# ledcurrentdriver.net
KiCad netlist of a schematic drawn in Altium Designer
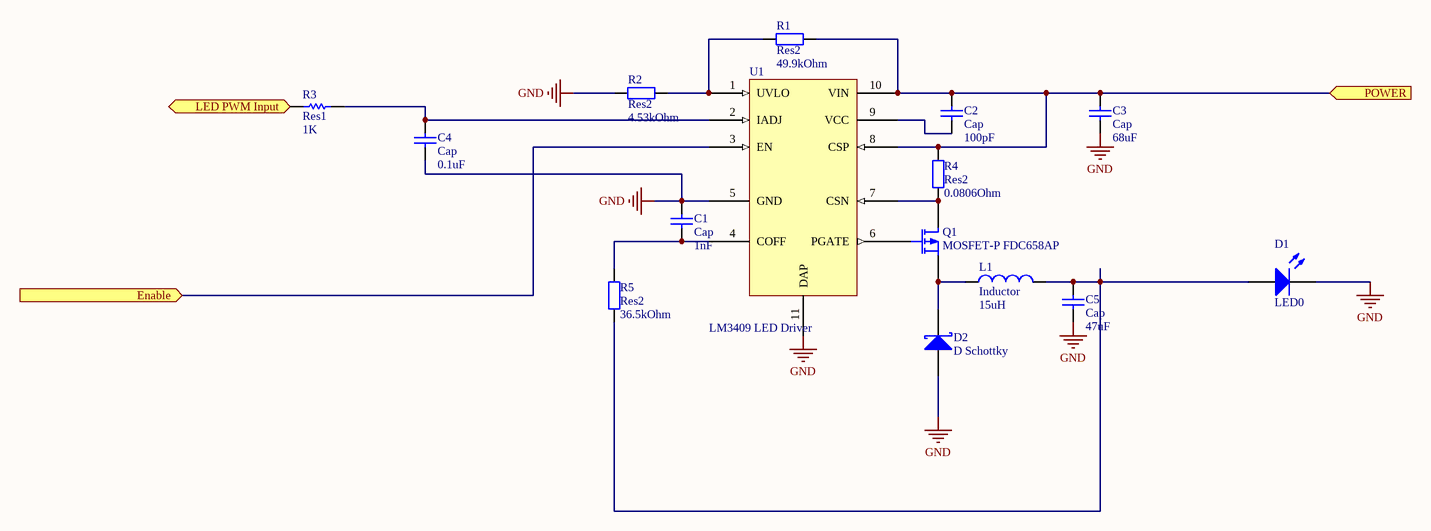
[diagram p0: ledcurrentdriver.SchDoc]

(export (version "E")
  (design (tool "Eeschema 10.0.6"))
  (components
    (comp (ref "C1")
      (value "Cap")
      (footprint "RAD-0.3")
      (description "Capacitor")
      (fields (field (name "ALTIUM_VALUE") "1nF") (field (name "PUBLISHER") "Altium Limited"))
      (libsource (lib "Miscellaneous Devices") (part "Cap"))
    )
    (comp (ref "C2")
      (value "Cap")
      (footprint "RAD-0.3")
      (description "Capacitor")
      (fields (field (name "ALTIUM_VALUE") "100pF") (field (name "PUBLISHER") "Altium Limited"))
      (libsource (lib "Miscellaneous Devices") (part "Cap"))
    )
    (comp (ref "C3")
      (value "Cap")
      (footprint "RAD-0.3")
      (description "Capacitor")
      (fields (field (name "ALTIUM_VALUE") "68uF") (field (name "PUBLISHER") "Altium Limited"))
      (libsource (lib "Miscellaneous Devices") (part "Cap"))
    )
    (comp (ref "C4")
      (value "Cap")
      (footprint "RAD-0.3")
      (description "Capacitor")
      (fields (field (name "ALTIUM_VALUE") "0.1uF") (field (name "PUBLISHER") "Altium Limited"))
      (libsource (lib "Miscellaneous Devices") (part "Cap"))
    )
    (comp (ref "C5")
      (value "Cap")
      (footprint "RAD-0.3")
      (description "Capacitor")
      (fields (field (name "ALTIUM_VALUE") "47uF") (field (name "PUBLISHER") "Altium Limited"))
      (libsource (lib "Miscellaneous Devices") (part "Cap"))
    )
    (comp (ref "D1")
      (value "LED0")
      (footprint "SML-01 (ROHM LED SERIES)")
      (description "Typical INFRARED GaAs LED")
      (fields (field (name "PUBLISHER") "Altium Limited"))
      (libsource (lib "Miscellaneous Devices") (part "LED0"))
    )
    (comp (ref "D2")
      (value "D Schottky")
      (footprint "SMB")
      (description "Schottky Diode")
      (fields (field (name "PUBLISHER") "Altium Limited"))
      (libsource (lib "Miscellaneous Devices") (part "D Schottky"))
    )
    (comp (ref "L1")
      (value "Inductor")
      (footprint "0402-A")
      (fields (field (name "ALTIUM_VALUE") "15uH") (field (name "PUBLISHER") "Altium Limited"))
      (libsource (lib "Miscellaneous Devices") (part "Inductor"))
    )
    (comp (ref "Q1")
      (value "MOSFET-P FDC658AP")
      (footprint "E3")
      (description "P-Channel MOSFET")
      (fields (field (name "PUBLISHER") "Altium Limited"))
      (libsource (lib "Miscellaneous Devices") (part "MOSFET-P"))
    )
    (comp (ref "R1")
      (value "Res2")
      (footprint "AXIAL-0.4")
      (description "Resistor")
      (fields (field (name "ALTIUM_VALUE") "49.9kOhm") (field (name "PUBLISHER") "Altium Limited"))
      (libsource (lib "") (part "Res2_1"))
    )
    (comp (ref "R2")
      (value "Res2")
      (footprint "AXIAL-0.4")
      (description "Resistor")
      (fields (field (name "ALTIUM_VALUE") "4.53kOhm") (field (name "PUBLISHER") "Altium Limited"))
      (libsource (lib "") (part "Res2_1"))
    )
    (comp (ref "R3")
      (value "Res1")
      (footprint "AXIAL-0.3")
      (description "Resistor")
      (fields (field (name "ALTIUM_VALUE") "1K") (field (name "PUBLISHER") "Altium Limited"))
      (libsource (lib "Miscellaneous Devices") (part "Res1"))
    )
    (comp (ref "R4")
      (value "Res2")
      (footprint "AXIAL-0.4")
      (description "Resistor")
      (fields (field (name "ALTIUM_VALUE") "0.0806Ohm") (field (name "PUBLISHER") "Altium Limited"))
      (libsource (lib "Miscellaneous Devices") (part "Res2"))
    )
    (comp (ref "R5")
      (value "Res2")
      (footprint "AXIAL-0.4")
      (description "Resistor")
      (fields (field (name "ALTIUM_VALUE") "36.5kOhm") (field (name "PUBLISHER") "Altium Limited"))
      (libsource (lib "Miscellaneous Devices") (part "Res2"))
    )
    (comp (ref "U1")
      (value "LM3409 LED Driver")
      (footprint "10eMSOP + thermal pad - LM3409")
      (description "PFET Buck Controller for High Power LED Drivers")
      (libsource (lib "LM3409") (part "LM3409"))
    )
  )
  (nets
    (net (code "1") (name "/Enable") (class "Default")
      (node (ref "U1") (pin "3") (pinfunction "EN_3") (pintype "input"))
    )
    (net (code "2") (name "/LED PWM Input") (class "Default")
      (node (ref "R3") (pin "1") (pinfunction "1_1") (pintype "passive"))
    )
    (net (code "5") (name "/POWER") (class "Default")
      (node (ref "C2") (pin "2") (pinfunction "2_2") (pintype "passive"))
      (node (ref "C3") (pin "2") (pinfunction "2_2") (pintype "passive"))
      (node (ref "R1") (pin "2") (pinfunction "2_2") (pintype "passive"))
      (node (ref "R4") (pin "2") (pinfunction "2_2") (pintype "passive"))
      (node (ref "U1") (pin "10") (pinfunction "VIN_10") (pintype "passive"))
      (node (ref "U1") (pin "8") (pinfunction "CSP_8") (pintype "input"))
    )
    (net (code "6") (name "GND") (class "Default")
      (node (ref "C1") (pin "2") (pinfunction "2_2") (pintype "passive"))
      (node (ref "C3") (pin "1") (pinfunction "1_1") (pintype "passive"))
      (node (ref "C4") (pin "2") (pinfunction "2_2") (pintype "passive"))
      (node (ref "C5") (pin "1") (pinfunction "1_1") (pintype "passive"))
      (node (ref "D1") (pin "2") (pinfunction "K_2") (pintype "passive"))
      (node (ref "D2") (pin "1") (pinfunction "A_1") (pintype "passive"))
      (node (ref "R2") (pin "1") (pinfunction "1_1") (pintype "passive"))
      (node (ref "U1") (pin "11") (pinfunction "DAP_11") (pintype "power_in"))
      (node (ref "U1") (pin "5") (pinfunction "GND_5") (pintype "power_in"))
    )
    (net (code "7") (name "Net-(D1-A)") (class "Default")
      (node (ref "C5") (pin "2") (pinfunction "2_2") (pintype "passive"))
      (node (ref "D1") (pin "1") (pinfunction "A_1") (pintype "passive"))
      (node (ref "L1") (pin "2") (pinfunction "2_2") (pintype "passive"))
      (node (ref "R5") (pin "1") (pinfunction "1_1") (pintype "passive"))
    )
    (net (code "8") (name "Net-(D2-K)") (class "Default")
      (node (ref "D2") (pin "2") (pinfunction "K_2") (pintype "passive"))
      (node (ref "L1") (pin "1") (pinfunction "1_1") (pintype "passive"))
      (node (ref "Q1") (pin "3") (pinfunction "S_3") (pintype "passive"))
    )
    (net (code "9") (name "Net-(Q1-D)") (class "Default")
      (node (ref "Q1") (pin "1") (pinfunction "D_1") (pintype "passive"))
      (node (ref "R4") (pin "1") (pinfunction "1_1") (pintype "passive"))
      (node (ref "U1") (pin "7") (pinfunction "CSN_7") (pintype "input"))
    )
    (net (code "10") (name "Net-(U1-COFF)") (class "Default")
      (node (ref "C1") (pin "1") (pinfunction "1_1") (pintype "passive"))
      (node (ref "R5") (pin "2") (pinfunction "2_2") (pintype "passive"))
      (node (ref "U1") (pin "4") (pinfunction "COFF_4") (pintype "passive"))
    )
    (net (code "11") (name "Net-(U1-IADJ)") (class "Default")
      (node (ref "C4") (pin "1") (pinfunction "1_1") (pintype "passive"))
      (node (ref "R3") (pin "2") (pinfunction "2_2") (pintype "passive"))
      (node (ref "U1") (pin "2") (pinfunction "IADJ_2") (pintype "input"))
    )
    (net (code "12") (name "Net-(U1-UVLO)") (class "Default")
      (node (ref "R1") (pin "1") (pinfunction "1_1") (pintype "passive"))
      (node (ref "R2") (pin "2") (pinfunction "2_2") (pintype "passive"))
      (node (ref "U1") (pin "1") (pinfunction "UVLO_1") (pintype "input"))
    )
    (net (code "13") (name "Net-(U1-VCC)") (class "Default")
      (node (ref "C2") (pin "1") (pinfunction "1_1") (pintype "passive"))
      (node (ref "U1") (pin "9") (pinfunction "VCC_9") (pintype "power_in"))
    )
    (net (code "14") (name "unconnected-(Q1-G-Pad2)") (class "Default")
      (node (ref "Q1") (pin "2") (pinfunction "G_2") (pintype "passive"))
    )
    (net (code "15") (name "unconnected-(U1-PGATE-Pad6)") (class "Default")
      (node (ref "U1") (pin "6") (pinfunction "PGATE_6") (pintype "output"))
    )
  )
)
